# ADC.net
KiCad netlist of a schematic drawn in Altium Designer
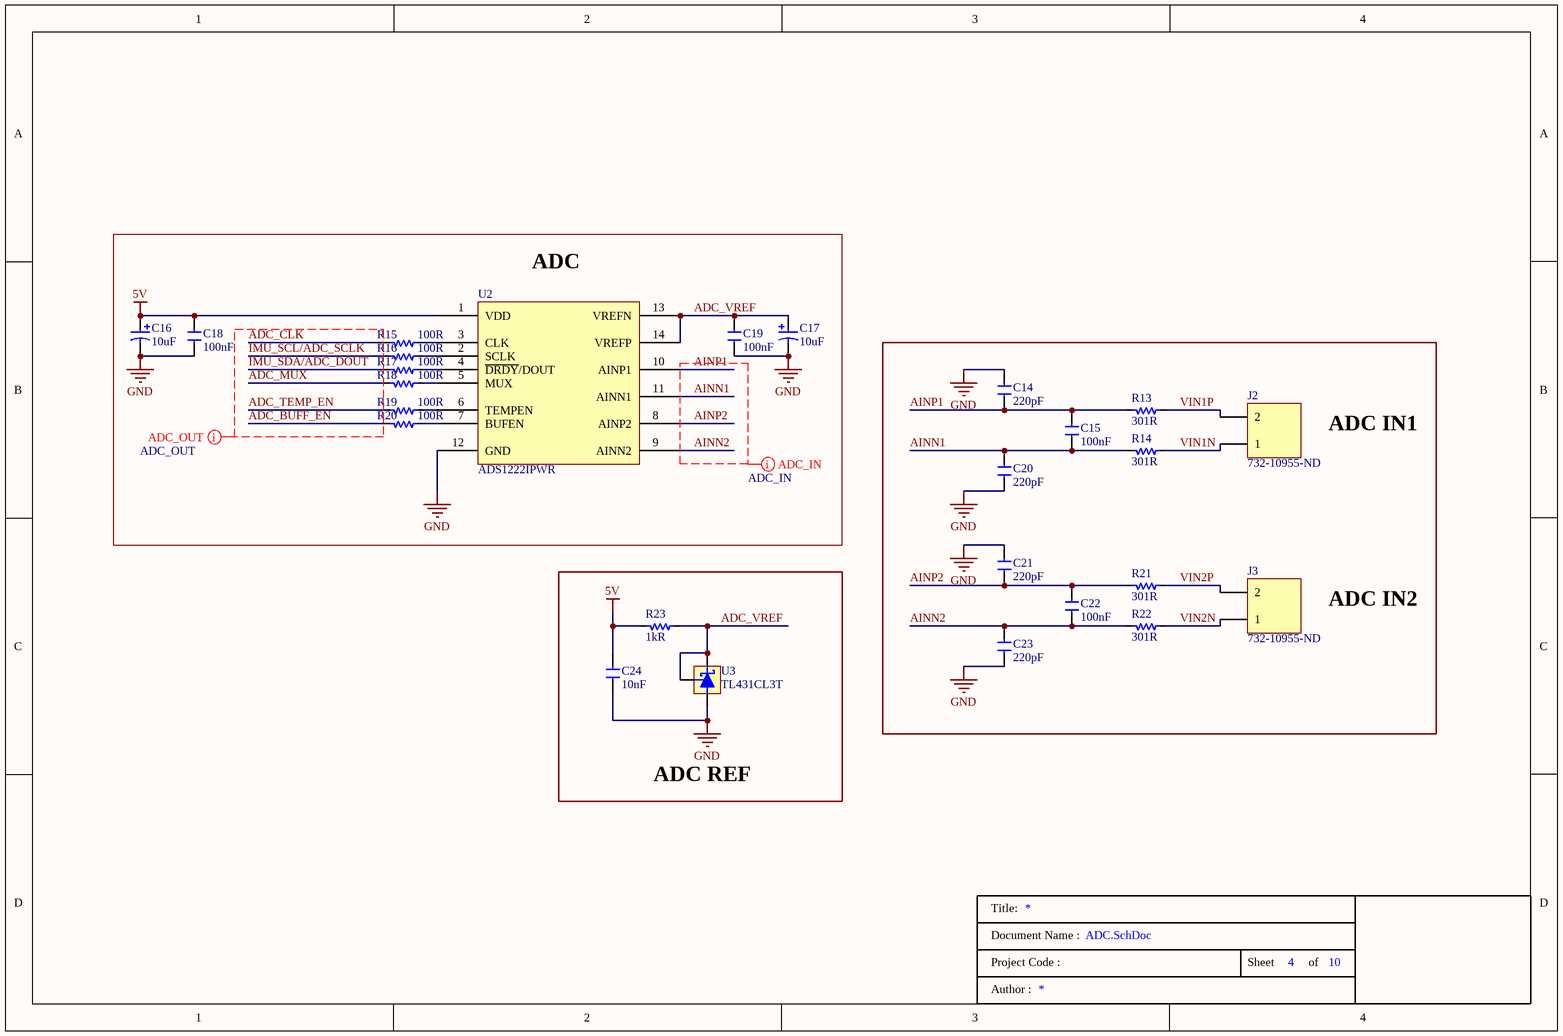
[diagram p0: ADC.SchDoc]

(export (version "E")
  (design (tool "Eeschema 10.0.6"))
  (components
    (comp (ref "C14")
      (value "CAP_220pF_50V_0805_C0G/NP0_CER")
      (footprint "0805_CAP")
      (description "CAP CER 220PF 50V C0G/NP0 0805")
      (fields
        (field (name "MANUFACTURER") "Samsung")
        (field (name "MANUFACTURER PART NUMBER") "CL21C221JBANNNC")
        (field (name "CAPACITANCE") "220pF")
      )
      (libsource (lib "Main Component Library") (part "CAP_220pF_50V_0805_C0G/NP0_CER"))
    )
    (comp (ref "C15")
      (value "CAP_0.1uF_50V_0805_X7R_CER")
      (footprint "0805_CAP")
      (description "Cap Ceramic 0.1uF 50V X7R 20% SMD 0805 125C Paper T/R")
      (fields
        (field (name "MANUFACTURER") "KEMET")
        (field (name "MANUFACTURER PART NUMBER") "C0805C104M5RACTU")
        (field (name "CAPACITANCE") "100nF")
      )
      (libsource (lib "Main Component Library") (part "CAP_0.1uF_50V_0805_X7R_CER"))
    )
    (comp (ref "C16")
      (value "CAP_10uF_10V_10%_1206_TANT")
      (footprint "1206_TANT_CAP")
      (description "Cap Tant Solid 10uF 10V A CASE 10% (3.2 X 1.6 X 1.6mm) Inward L SMD 3216-18 3 Ohm 125C T/R")
      (fields
        (field (name "MANUFACTURER") "Kyocera AVX")
        (field (name "MANUFACTURER PART NUMBER") "TAJA106K010SNJ")
        (field (name "CAPACITANCE") "10uF")
      )
      (libsource (lib "Main Component Library") (part "CAP_10uF_10V_10%_1206_TANT"))
    )
    (comp (ref "C17")
      (value "CAP_10uF_10V_10%_1206_TANT")
      (footprint "1206_TANT_CAP")
      (description "Cap Tant Solid 10uF 10V A CASE 10% (3.2 X 1.6 X 1.6mm) Inward L SMD 3216-18 3 Ohm 125C T/R")
      (fields
        (field (name "MANUFACTURER") "Kyocera AVX")
        (field (name "MANUFACTURER PART NUMBER") "TAJA106K010SNJ")
        (field (name "CAPACITANCE") "10uF")
      )
      (libsource (lib "Main Component Library") (part "CAP_10uF_10V_10%_1206_TANT"))
    )
    (comp (ref "C18")
      (value "CAP_0.1uF_50V_0805_X7R_CER")
      (footprint "0805_CAP")
      (description "Cap Ceramic 0.1uF 50V X7R 20% SMD 0805 125C Paper T/R")
      (fields
        (field (name "MANUFACTURER") "KEMET")
        (field (name "MANUFACTURER PART NUMBER") "C0805C104M5RACTU")
        (field (name "CAPACITANCE") "100nF")
      )
      (libsource (lib "Main Component Library") (part "CAP_0.1uF_50V_0805_X7R_CER"))
    )
    (comp (ref "C19")
      (value "CAP_0.1uF_50V_0805_X7R_CER")
      (footprint "0805_CAP")
      (description "Cap Ceramic 0.1uF 50V X7R 20% SMD 0805 125C Paper T/R")
      (fields
        (field (name "MANUFACTURER") "KEMET")
        (field (name "MANUFACTURER PART NUMBER") "C0805C104M5RACTU")
        (field (name "CAPACITANCE") "100nF")
      )
      (libsource (lib "Main Component Library") (part "CAP_0.1uF_50V_0805_X7R_CER"))
    )
    (comp (ref "C20")
      (value "CAP_220pF_50V_0805_C0G/NP0_CER")
      (footprint "0805_CAP")
      (description "CAP CER 220PF 50V C0G/NP0 0805")
      (fields
        (field (name "MANUFACTURER") "Samsung")
        (field (name "MANUFACTURER PART NUMBER") "CL21C221JBANNNC")
        (field (name "CAPACITANCE") "220pF")
      )
      (libsource (lib "Main Component Library") (part "CAP_220pF_50V_0805_C0G/NP0_CER"))
    )
    (comp (ref "C21")
      (value "CAP_220pF_50V_0805_C0G/NP0_CER")
      (footprint "0805_CAP")
      (description "CAP CER 220PF 50V C0G/NP0 0805")
      (fields
        (field (name "MANUFACTURER") "Samsung")
        (field (name "MANUFACTURER PART NUMBER") "CL21C221JBANNNC")
        (field (name "CAPACITANCE") "220pF")
      )
      (libsource (lib "Main Component Library") (part "CAP_220pF_50V_0805_C0G/NP0_CER"))
    )
    (comp (ref "C22")
      (value "CAP_0.1uF_50V_0805_X7R_CER")
      (footprint "0805_CAP")
      (description "Cap Ceramic 0.1uF 50V X7R 20% SMD 0805 125C Paper T/R")
      (fields
        (field (name "MANUFACTURER") "KEMET")
        (field (name "MANUFACTURER PART NUMBER") "C0805C104M5RACTU")
        (field (name "CAPACITANCE") "100nF")
      )
      (libsource (lib "Main Component Library") (part "CAP_0.1uF_50V_0805_X7R_CER"))
    )
    (comp (ref "C23")
      (value "CAP_220pF_50V_0805_C0G/NP0_CER")
      (footprint "0805_CAP")
      (description "CAP CER 220PF 50V C0G/NP0 0805")
      (fields
        (field (name "MANUFACTURER") "Samsung")
        (field (name "MANUFACTURER PART NUMBER") "CL21C221JBANNNC")
        (field (name "CAPACITANCE") "220pF")
      )
      (libsource (lib "Main Component Library") (part "CAP_220pF_50V_0805_C0G/NP0_CER"))
    )
    (comp (ref "C24")
      (value "CAP_10nF_%10_50V_0805_X7R_CER")
      (footprint "0805_CAP")
      (description "CAP CER 10000PF 50V X7R 0805")
      (fields
        (field (name "MANUFACTURER") "Samsung")
        (field (name "MANUFACTURER PART NUMBER") "CL21B103KBANNNC")
        (field (name "CAPACITANCE") "10nF")
      )
      (libsource (lib "Main Schematic Library") (part "CAP_10nF_%10_50V_0805_X7R_CER"))
    )
    (comp (ref "J2")
      (value "CONN_1X2_Terminal Block")
      (footprint "1x2_TERMINAL BLOCK")
      (description "Series 1377 - 5.00 mm Horizontal Entry with Pressure Clamp WR-TBL, 2 pin")
      (fields
        (field (name "MANUFACTURER") "Wurth Electronics")
        (field (name "MANUFACTURER PART NUMBER") "691137710002")
        (field (name "SUPPLIER PART NUMBER 1") "732-10955-ND")
      )
      (libsource (lib "Main Schematic Library") (part "CONN_1X2_Terminal Block"))
    )
    (comp (ref "J3")
      (value "CONN_1X2_Terminal Block")
      (footprint "1x2_TERMINAL BLOCK")
      (description "Series 1377 - 5.00 mm Horizontal Entry with Pressure Clamp WR-TBL, 2 pin")
      (fields
        (field (name "MANUFACTURER") "Wurth Electronics")
        (field (name "MANUFACTURER PART NUMBER") "691137710002")
        (field (name "SUPPLIER PART NUMBER 1") "732-10955-ND")
      )
      (libsource (lib "Main Schematic Library") (part "CONN_1X2_Terminal Block"))
    )
    (comp (ref "R13")
      (value "RES_301 OHM_1%_0805_1/8W")
      (footprint "0805_RES")
      (description "Res Thick Film 0805 301 Ohm 1% 1/8W ±100ppm/°C Molded SMD SMD Paper T/R")
      (fields
        (field (name "MANUFACTURER") "Yageo")
        (field (name "MANUFACTURER PART NUMBER") "RC0805FR-10301RL")
        (field (name "RESISTANCE") "301R")
      )
      (libsource (lib "Main Schematic Library") (part "RES_301 OHM_1%_0805_1/8W"))
    )
    (comp (ref "R14")
      (value "RES_301 OHM_1%_0805_1/8W")
      (footprint "0805_RES")
      (description "Res Thick Film 0805 301 Ohm 1% 1/8W ±100ppm/°C Molded SMD SMD Paper T/R")
      (fields
        (field (name "MANUFACTURER") "Yageo")
        (field (name "MANUFACTURER PART NUMBER") "RC0805FR-10301RL")
        (field (name "RESISTANCE") "301R")
      )
      (libsource (lib "Main Schematic Library") (part "RES_301 OHM_1%_0805_1/8W"))
    )
    (comp (ref "R15")
      (value "RES_100 OHM_1%_0805_1/8W")
      (footprint "0805_RES")
      (description "贴片电阻 100Ω ± 1.00% 0.125W ± 100ppm/℃ 0805")
      (fields
        (field (name "MANUFACTURER") "Yageo")
        (field (name "MANUFACTURER PART NUMBER") "RC0805FR-07100RL")
        (field (name "RESISTANCE") "100R")
      )
      (libsource (lib "Main Component Library") (part "RES_100 OHM_1%_0805_1/8W"))
    )
    (comp (ref "R16")
      (value "RES_100 OHM_1%_0805_1/8W")
      (footprint "0805_RES")
      (description "贴片电阻 100Ω ± 1.00% 0.125W ± 100ppm/℃ 0805")
      (fields
        (field (name "MANUFACTURER") "Yageo")
        (field (name "MANUFACTURER PART NUMBER") "RC0805FR-07100RL")
        (field (name "RESISTANCE") "100R")
      )
      (libsource (lib "Main Component Library") (part "RES_100 OHM_1%_0805_1/8W"))
    )
    (comp (ref "R17")
      (value "RES_100 OHM_1%_0805_1/8W")
      (footprint "0805_RES")
      (description "贴片电阻 100Ω ± 1.00% 0.125W ± 100ppm/℃ 0805")
      (fields
        (field (name "MANUFACTURER") "Yageo")
        (field (name "MANUFACTURER PART NUMBER") "RC0805FR-07100RL")
        (field (name "RESISTANCE") "100R")
      )
      (libsource (lib "Main Component Library") (part "RES_100 OHM_1%_0805_1/8W"))
    )
    (comp (ref "R18")
      (value "RES_100 OHM_1%_0805_1/8W")
      (footprint "0805_RES")
      (description "贴片电阻 100Ω ± 1.00% 0.125W ± 100ppm/℃ 0805")
      (fields
        (field (name "MANUFACTURER") "Yageo")
        (field (name "MANUFACTURER PART NUMBER") "RC0805FR-07100RL")
        (field (name "RESISTANCE") "100R")
      )
      (libsource (lib "Main Component Library") (part "RES_100 OHM_1%_0805_1/8W"))
    )
    (comp (ref "R19")
      (value "RES_100 OHM_1%_0805_1/8W")
      (footprint "0805_RES")
      (description "贴片电阻 100Ω ± 1.00% 0.125W ± 100ppm/℃ 0805")
      (fields
        (field (name "MANUFACTURER") "Yageo")
        (field (name "MANUFACTURER PART NUMBER") "RC0805FR-07100RL")
        (field (name "RESISTANCE") "100R")
      )
      (libsource (lib "Main Component Library") (part "RES_100 OHM_1%_0805_1/8W"))
    )
    (comp (ref "R20")
      (value "RES_100 OHM_1%_0805_1/8W")
      (footprint "0805_RES")
      (description "贴片电阻 100Ω ± 1.00% 0.125W ± 100ppm/℃ 0805")
      (fields
        (field (name "MANUFACTURER") "Yageo")
        (field (name "MANUFACTURER PART NUMBER") "RC0805FR-07100RL")
        (field (name "RESISTANCE") "100R")
      )
      (libsource (lib "Main Component Library") (part "RES_100 OHM_1%_0805_1/8W"))
    )
    (comp (ref "R21")
      (value "RES_301 OHM_1%_0805_1/8W")
      (footprint "0805_RES")
      (description "Res Thick Film 0805 301 Ohm 1% 1/8W ±100ppm/°C Molded SMD SMD Paper T/R")
      (fields
        (field (name "MANUFACTURER") "Yageo")
        (field (name "MANUFACTURER PART NUMBER") "RC0805FR-10301RL")
        (field (name "RESISTANCE") "301R")
      )
      (libsource (lib "Main Schematic Library") (part "RES_301 OHM_1%_0805_1/8W"))
    )
    (comp (ref "R22")
      (value "RES_301 OHM_1%_0805_1/8W")
      (footprint "0805_RES")
      (description "Res Thick Film 0805 301 Ohm 1% 1/8W ±100ppm/°C Molded SMD SMD Paper T/R")
      (fields
        (field (name "MANUFACTURER") "Yageo")
        (field (name "MANUFACTURER PART NUMBER") "RC0805FR-10301RL")
        (field (name "RESISTANCE") "301R")
      )
      (libsource (lib "Main Schematic Library") (part "RES_301 OHM_1%_0805_1/8W"))
    )
    (comp (ref "R23")
      (value "RES_1K OHM_1%_0805_1/8W")
      (footprint "0805_RES")
      (description "贴片电阻 1000Ω ± 1.00% 0.125W ± 100ppm/℃ 0805")
      (fields
        (field (name "MANUFACTURER") "Yageo")
        (field (name "MANUFACTURER PART NUMBER") "RC0805FR-071KL")
        (field (name "RESISTANCE") "1kR")
      )
      (libsource (lib "Main Component Library") (part "RES_1K OHM_1%_0805_1/8W"))
    )
    (comp (ref "U2")
      (value "ADS1222IPWR")
      (footprint "TSOP65P640X120-14N")
      (description "24 Bit Analog to Digital Converter 2 Input 1 Sigma-Delta 14-TSSOP")
      (fields (field (name "MANUFACTURER") "Texas Instruments"))
      (libsource (lib "Main Component Library") (part "IC_ADS1222IPWR"))
    )
    (comp (ref "U3")
      (value "IC_VREF_SHUNT_TL431CL3T")
      (footprint "SOT95P237X112-3N")
      (description "V-Ref Adjustable 2.495V to 36V 100mA 3-Pin SOT-23 T/R")
      (fields
        (field (name "MANUFACTURER") "STMicroelectronics")
        (field (name "TOLERANCE") "2.21%")
        (field (name "MANUFACTURER PART NUMBER") "TL431CL3T")
      )
      (libsource (lib "Main Component Library") (part "IC_VREF_SHUNT_TL431CL3T"))
    )
  )
  (nets
    (net (code "1") (name "/ADC_BUFF_EN") (class "Default")
      (node (ref "R20") (pin "1") (pinfunction "1_1") (pintype "passive"))
    )
    (net (code "2") (name "/ADC_CLK") (class "Default")
      (node (ref "R15") (pin "1") (pinfunction "1_1") (pintype "passive"))
    )
    (net (code "3") (name "/ADC_MUX") (class "Default")
      (node (ref "R18") (pin "1") (pinfunction "1_1") (pintype "passive"))
    )
    (net (code "4") (name "/ADC_TEMP_EN") (class "Default")
      (node (ref "R19") (pin "1") (pinfunction "1_1") (pintype "passive"))
    )
    (net (code "5") (name "/ADC_VREF") (class "Default")
      (node (ref "C17") (pin "1") (pinfunction "1_1") (pintype "passive"))
      (node (ref "C19") (pin "2") (pinfunction "2_2") (pintype "passive"))
      (node (ref "R23") (pin "2") (pinfunction "2_2") (pintype "passive"))
      (node (ref "U2") (pin "13") (pinfunction "VREFN_13") (pintype "passive"))
      (node (ref "U2") (pin "14") (pinfunction "VREFP_14") (pintype "passive"))
      (node (ref "U3") (pin "1") (pinfunction "CATHODE_1") (pintype "passive"))
      (node (ref "U3") (pin "2") (pinfunction "REF_2") (pintype "passive"))
    )
    (net (code "6") (name "/AINN1") (class "Default")
      (node (ref "C15") (pin "1") (pinfunction "1_1") (pintype "passive"))
      (node (ref "C20") (pin "2") (pinfunction "2_2") (pintype "passive"))
      (node (ref "R14") (pin "1") (pinfunction "1_1") (pintype "passive"))
      (node (ref "U2") (pin "11") (pinfunction "AINN1_11") (pintype "passive"))
    )
    (net (code "7") (name "/AINN2") (class "Default")
      (node (ref "C22") (pin "1") (pinfunction "1_1") (pintype "passive"))
      (node (ref "C23") (pin "2") (pinfunction "2_2") (pintype "passive"))
      (node (ref "R22") (pin "1") (pinfunction "1_1") (pintype "passive"))
      (node (ref "U2") (pin "9") (pinfunction "AINN2_9") (pintype "passive"))
    )
    (net (code "8") (name "/AINP1") (class "Default")
      (node (ref "C14") (pin "1") (pinfunction "1_1") (pintype "passive"))
      (node (ref "C15") (pin "2") (pinfunction "2_2") (pintype "passive"))
      (node (ref "R13") (pin "1") (pinfunction "1_1") (pintype "passive"))
      (node (ref "U2") (pin "10") (pinfunction "AINP1_10") (pintype "passive"))
    )
    (net (code "9") (name "/AINP2") (class "Default")
      (node (ref "C21") (pin "1") (pinfunction "1_1") (pintype "passive"))
      (node (ref "C22") (pin "2") (pinfunction "2_2") (pintype "passive"))
      (node (ref "R21") (pin "1") (pinfunction "1_1") (pintype "passive"))
      (node (ref "U2") (pin "8") (pinfunction "AINP2_8") (pintype "passive"))
    )
    (net (code "10") (name "/IMU_SCL{slash}ADC_SCLK") (class "Default")
      (node (ref "R16") (pin "1") (pinfunction "1_1") (pintype "passive"))
    )
    (net (code "11") (name "/IMU_SDA{slash}ADC_DOUT") (class "Default")
      (node (ref "R17") (pin "1") (pinfunction "1_1") (pintype "passive"))
    )
    (net (code "12") (name "/VIN1N") (class "Default")
      (node (ref "J2") (pin "1") (pinfunction "1_1") (pintype "passive"))
      (node (ref "R14") (pin "2") (pinfunction "2_2") (pintype "passive"))
    )
    (net (code "13") (name "/VIN1P") (class "Default")
      (node (ref "J2") (pin "2") (pinfunction "2_2") (pintype "passive"))
      (node (ref "R13") (pin "2") (pinfunction "2_2") (pintype "passive"))
    )
    (net (code "14") (name "/VIN2N") (class "Default")
      (node (ref "J3") (pin "1") (pinfunction "1_1") (pintype "passive"))
      (node (ref "R22") (pin "2") (pinfunction "2_2") (pintype "passive"))
    )
    (net (code "15") (name "/VIN2P") (class "Default")
      (node (ref "J3") (pin "2") (pinfunction "2_2") (pintype "passive"))
      (node (ref "R21") (pin "2") (pinfunction "2_2") (pintype "passive"))
    )
    (net (code "16") (name "5V") (class "Default")
      (node (ref "C16") (pin "1") (pinfunction "1_1") (pintype "passive"))
      (node (ref "C18") (pin "2") (pinfunction "2_2") (pintype "passive"))
      (node (ref "C24") (pin "2") (pinfunction "2_2") (pintype "passive"))
      (node (ref "R23") (pin "1") (pinfunction "1_1") (pintype "passive"))
      (node (ref "U2") (pin "1") (pinfunction "VDD_1") (pintype "passive"))
    )
    (net (code "17") (name "GND") (class "Default")
      (node (ref "C14") (pin "2") (pinfunction "2_2") (pintype "passive"))
      (node (ref "C16") (pin "2") (pinfunction "2_2") (pintype "passive"))
      (node (ref "C17") (pin "2") (pinfunction "2_2") (pintype "passive"))
      (node (ref "C18") (pin "1") (pinfunction "1_1") (pintype "passive"))
      (node (ref "C19") (pin "1") (pinfunction "1_1") (pintype "passive"))
      (node (ref "C20") (pin "1") (pinfunction "1_1") (pintype "passive"))
      (node (ref "C21") (pin "2") (pinfunction "2_2") (pintype "passive"))
      (node (ref "C23") (pin "1") (pinfunction "1_1") (pintype "passive"))
      (node (ref "C24") (pin "1") (pinfunction "1_1") (pintype "passive"))
      (node (ref "U2") (pin "12") (pinfunction "GND_12") (pintype "passive"))
      (node (ref "U3") (pin "3") (pinfunction "ANODE_3") (pintype "passive"))
    )
    (net (code "18") (name "Net-(U2-BUFEN)") (class "Default")
      (node (ref "R20") (pin "2") (pinfunction "2_2") (pintype "passive"))
      (node (ref "U2") (pin "7") (pinfunction "BUFEN_7") (pintype "passive"))
    )
    (net (code "19") (name "Net-(U2-CLK)") (class "Default")
      (node (ref "R15") (pin "2") (pinfunction "2_2") (pintype "passive"))
      (node (ref "U2") (pin "3") (pinfunction "CLK_3") (pintype "passive"))
    )
    (net (code "20") (name "Net-(U2-MUX)") (class "Default")
      (node (ref "R18") (pin "2") (pinfunction "2_2") (pintype "passive"))
      (node (ref "U2") (pin "5") (pinfunction "MUX_5") (pintype "passive"))
    )
    (net (code "21") (name "Net-(U2-SCLK)") (class "Default")
      (node (ref "R16") (pin "2") (pinfunction "2_2") (pintype "passive"))
      (node (ref "U2") (pin "2") (pinfunction "SCLK_2") (pintype "passive"))
    )
    (net (code "22") (name "Net-(U2-TEMPEN)") (class "Default")
      (node (ref "R19") (pin "2") (pinfunction "2_2") (pintype "passive"))
      (node (ref "U2") (pin "6") (pinfunction "TEMPEN_6") (pintype "passive"))
    )
    (net (code "23") (name "Net-(U2-~{DRDY}{slash}DOUT)") (class "Default")
      (node (ref "R17") (pin "2") (pinfunction "2_2") (pintype "passive"))
      (node (ref "U2") (pin "4") (pinfunction "~{DRDY}/DOUT_4") (pintype "passive"))
    )
  )
)
